# M220.net
KiCad netlist of a schematic drawn in EAGLE
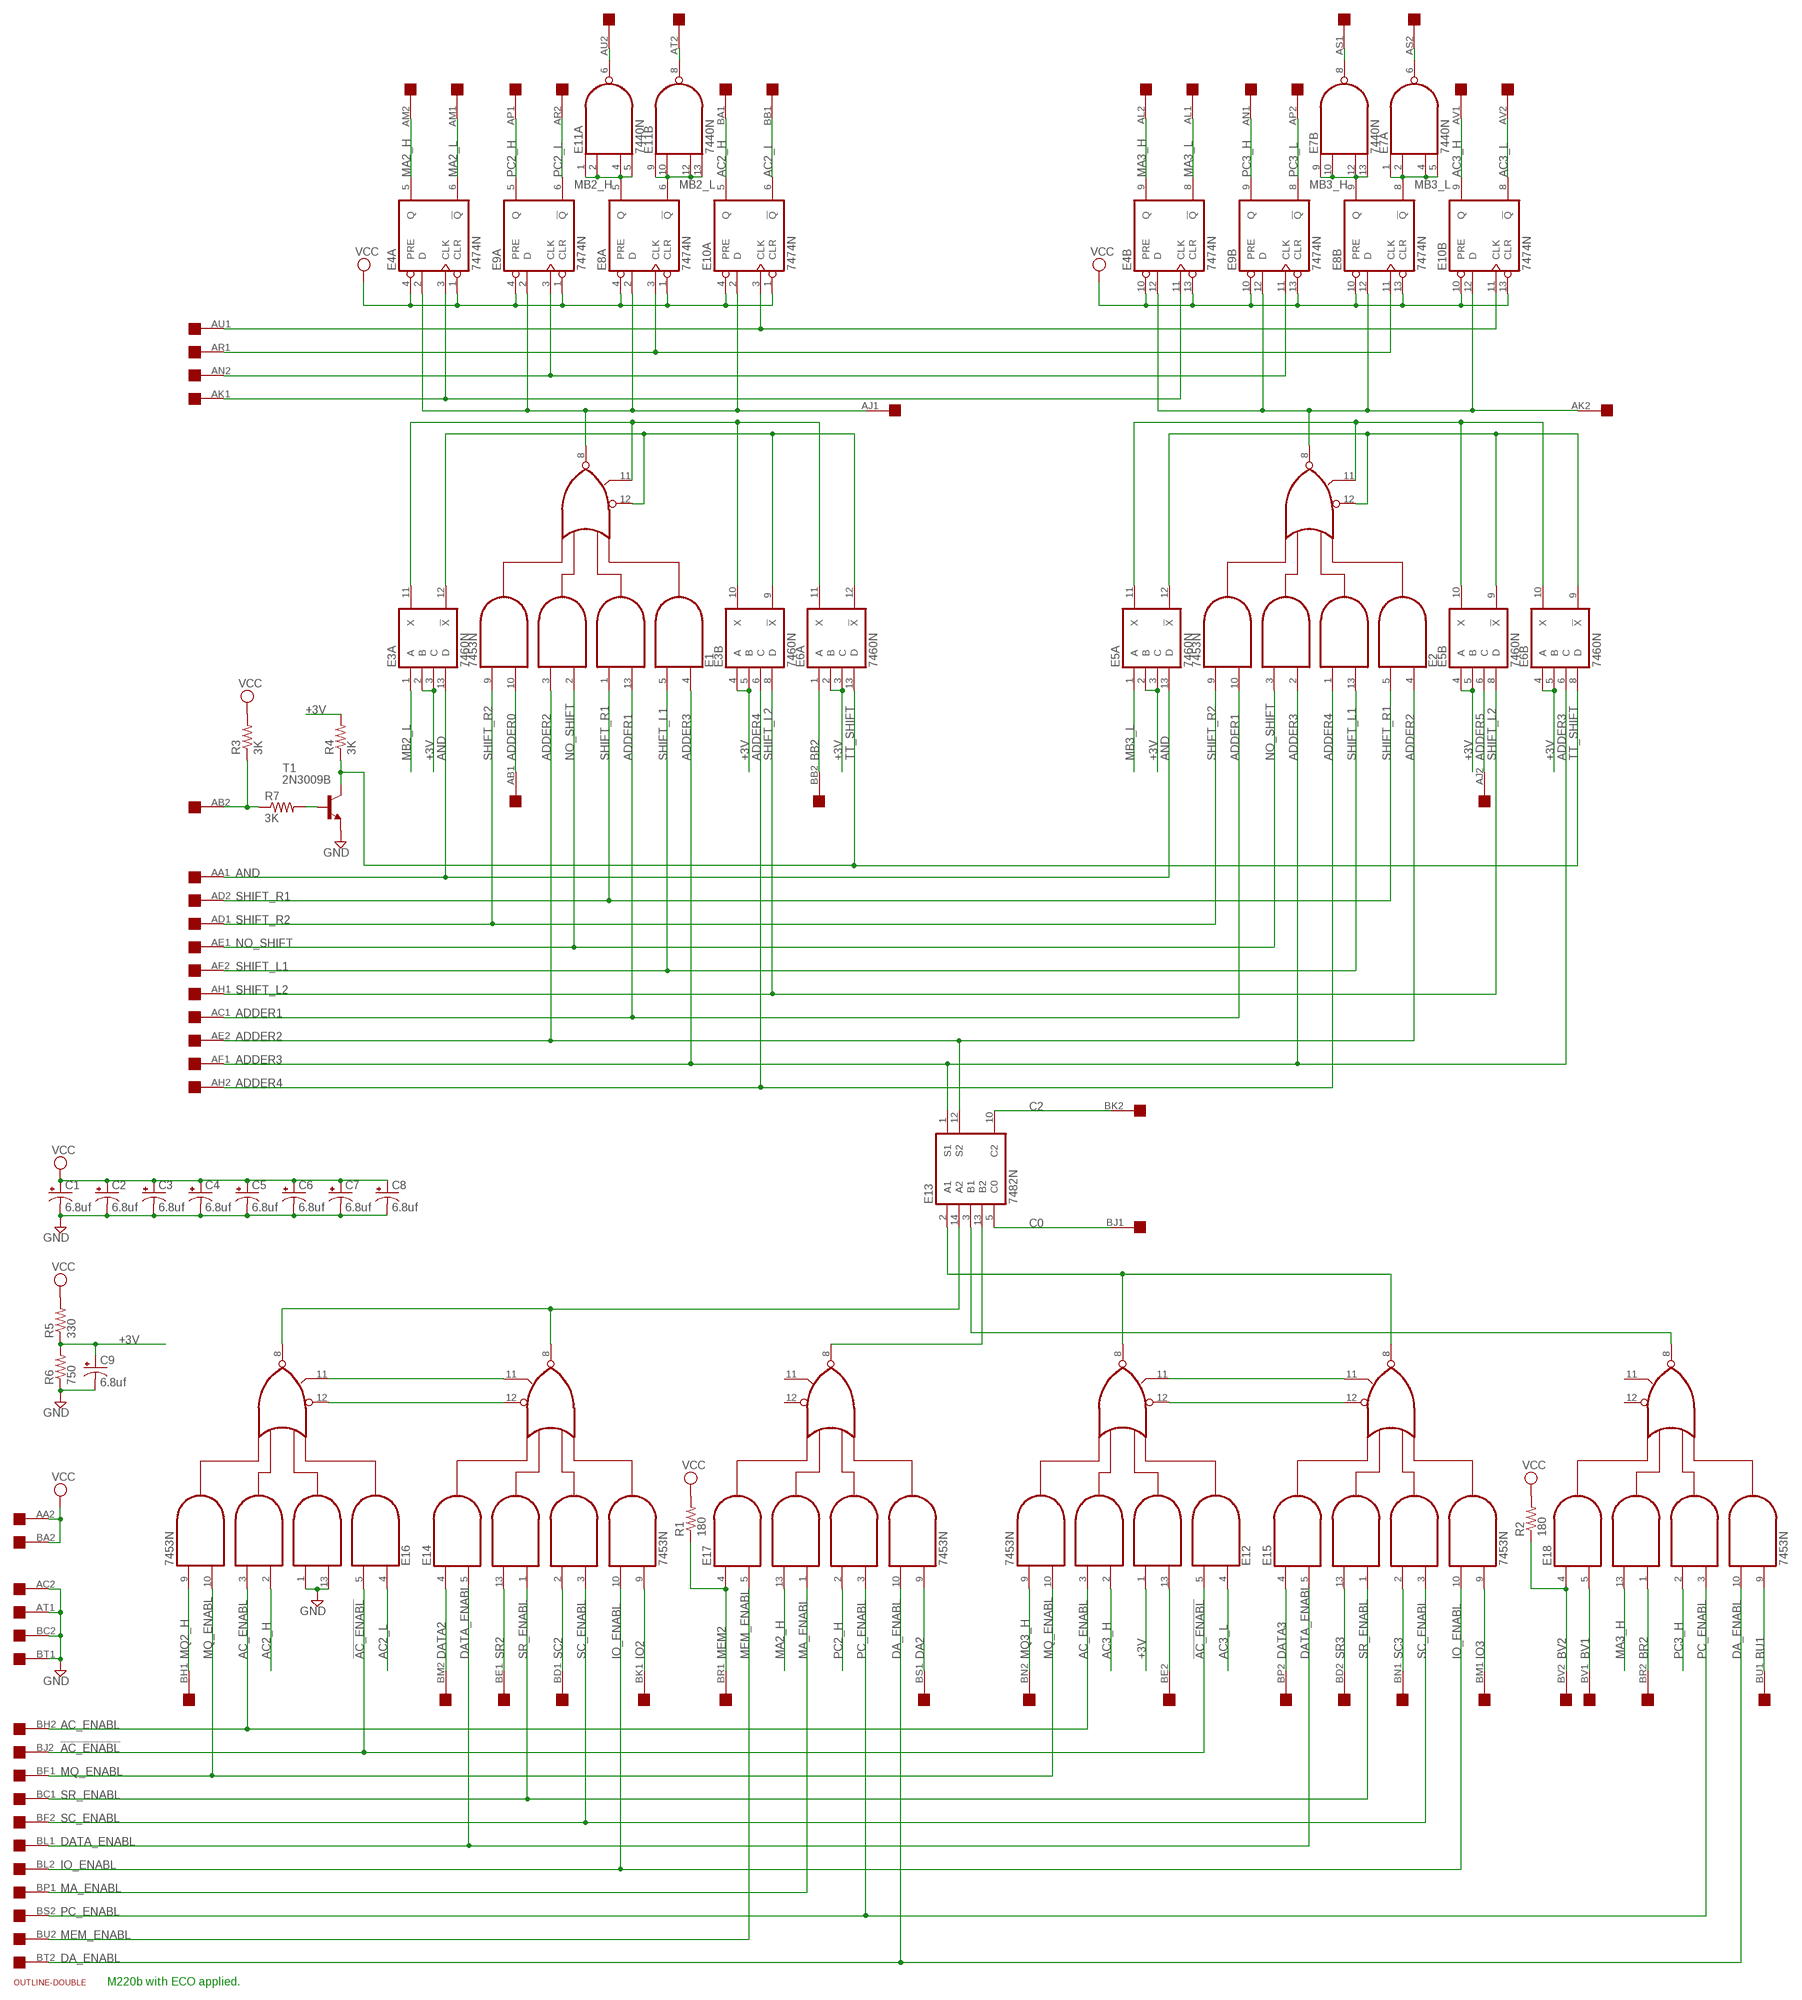
[diagram p0: schematic, sheet 1]

(export (version "E")
  (design (tool "Eeschema 10.0.6"))
  (components
    (comp (ref "C1")
      (value "6.8uf")
      (footprint "eagle-import:E15-5")
      (libsource (lib "eagle-import") (part "CPOL-USE15-5AXIAL"))
    )
    (comp (ref "C2")
      (value "6.8uf")
      (footprint "eagle-import:E15-5")
      (libsource (lib "eagle-import") (part "CPOL-USE15-5AXIAL"))
    )
    (comp (ref "C3")
      (value "6.8uf")
      (footprint "eagle-import:E15-5")
      (libsource (lib "eagle-import") (part "CPOL-USE15-5AXIAL"))
    )
    (comp (ref "C4")
      (value "6.8uf")
      (footprint "eagle-import:E15-5")
      (libsource (lib "eagle-import") (part "CPOL-USE15-5AXIAL"))
    )
    (comp (ref "C5")
      (value "6.8uf")
      (footprint "eagle-import:E15-5")
      (libsource (lib "eagle-import") (part "CPOL-USE15-5AXIAL"))
    )
    (comp (ref "C6")
      (value "6.8uf")
      (footprint "eagle-import:E15-5")
      (libsource (lib "eagle-import") (part "CPOL-USE15-5AXIAL"))
    )
    (comp (ref "C7")
      (value "6.8uf")
      (footprint "eagle-import:E15-5")
      (libsource (lib "eagle-import") (part "CPOL-USE15-5AXIAL"))
    )
    (comp (ref "C8")
      (value "6.8uf")
      (footprint "eagle-import:E15-5")
      (libsource (lib "eagle-import") (part "CPOL-USE15-5AXIAL"))
    )
    (comp (ref "C9")
      (value "6.8uf")
      (footprint "eagle-import:E15-5")
      (libsource (lib "eagle-import") (part "CPOL-USE15-5AXIAL"))
    )
    (comp (ref "E1")
      (value "7453N")
      (footprint "eagle-import:DIL14")
      (libsource (lib "eagle-import") (part "7453N"))
    )
    (comp (ref "E2")
      (value "7453N")
      (footprint "eagle-import:DIL14")
      (libsource (lib "eagle-import") (part "7453N"))
    )
    (comp (ref "E3")
      (value "7460N")
      (footprint "eagle-import:DIL14")
      (libsource (lib "eagle-import") (part "7460N"))
    )
    (comp (ref "E4")
      (value "7474N")
      (footprint "eagle-import:DIL14")
      (libsource (lib "eagle-import") (part "7474NS"))
    )
    (comp (ref "E5")
      (value "7460N")
      (footprint "eagle-import:DIL14")
      (libsource (lib "eagle-import") (part "7460N"))
    )
    (comp (ref "E6")
      (value "7460N")
      (footprint "eagle-import:DIL14")
      (libsource (lib "eagle-import") (part "7460N"))
    )
    (comp (ref "E7")
      (value "7440N")
      (footprint "eagle-import:DIL14")
      (libsource (lib "eagle-import") (part "7420NS"))
    )
    (comp (ref "E8")
      (value "7474N")
      (footprint "eagle-import:DIL14")
      (libsource (lib "eagle-import") (part "7474NS"))
    )
    (comp (ref "E9")
      (value "7474N")
      (footprint "eagle-import:DIL14")
      (libsource (lib "eagle-import") (part "7474NS"))
    )
    (comp (ref "E10")
      (value "7474N")
      (footprint "eagle-import:DIL14")
      (libsource (lib "eagle-import") (part "7474NS"))
    )
    (comp (ref "E11")
      (value "7440N")
      (footprint "eagle-import:DIL14")
      (libsource (lib "eagle-import") (part "7420NS"))
    )
    (comp (ref "E12")
      (value "7453N")
      (footprint "eagle-import:DIL14")
      (libsource (lib "eagle-import") (part "7453N"))
    )
    (comp (ref "E13")
      (value "7482N")
      (footprint "eagle-import:DIL14")
      (libsource (lib "eagle-import") (part "7482N"))
    )
    (comp (ref "E14")
      (value "7453N")
      (footprint "eagle-import:DIL14")
      (libsource (lib "eagle-import") (part "7453N"))
    )
    (comp (ref "E15")
      (value "7453N")
      (footprint "eagle-import:DIL14")
      (libsource (lib "eagle-import") (part "7453N"))
    )
    (comp (ref "E16")
      (value "7453N")
      (footprint "eagle-import:DIL14")
      (libsource (lib "eagle-import") (part "7453N"))
    )
    (comp (ref "E17")
      (value "7453N")
      (footprint "eagle-import:DIL14")
      (libsource (lib "eagle-import") (part "7453N"))
    )
    (comp (ref "E18")
      (value "7453N")
      (footprint "eagle-import:DIL14")
      (libsource (lib "eagle-import") (part "7453N"))
    )
    (comp (ref "R1")
      (value "180")
      (footprint "eagle-import:0207_10")
      (libsource (lib "eagle-import") (part "R-US_0207/10"))
    )
    (comp (ref "R2")
      (value "180")
      (footprint "eagle-import:0207_10")
      (libsource (lib "eagle-import") (part "R-US_0207/10"))
    )
    (comp (ref "R3")
      (value "3K")
      (footprint "eagle-import:0207_10")
      (libsource (lib "eagle-import") (part "R-US_0207/10"))
    )
    (comp (ref "R4")
      (value "3K")
      (footprint "eagle-import:0207_10")
      (libsource (lib "eagle-import") (part "R-US_0207/10"))
    )
    (comp (ref "R5")
      (value "330")
      (footprint "eagle-import:0207_10")
      (libsource (lib "eagle-import") (part "R-US_0207/10"))
    )
    (comp (ref "R6")
      (value "750")
      (footprint "eagle-import:0207_10")
      (libsource (lib "eagle-import") (part "R-US_0207/10"))
    )
    (comp (ref "R7")
      (value "3K")
      (footprint "eagle-import:0207_10")
      (libsource (lib "eagle-import") (part "R-US_0207/10"))
    )
    (comp (ref "T1")
      (value "2N3009B")
      (footprint "eagle-import:TO5")
      (libsource (lib "eagle-import") (part "2N1613"))
    )
    (comp (ref "U$1")
      (value "DOUBLE")
      (footprint "eagle-import:EDGE-CON4")
      (libsource (lib "eagle-import") (part "DOUBLE"))
    )
    (comp (ref "U$2")
      (value "OUTLINE-DOUBLE")
      (footprint "eagle-import:DOUBLE")
      (libsource (lib "eagle-import") (part "OUTLINE-DOUBLE"))
    )
  )
  (nets
    (net (code "1") (name "/+3V") (class "Default")
      (node (ref "C9") (pin "+") (pinfunction "+_+") (pintype "passive"))
      (node (ref "E12") (pin "1") (pinfunction "I4_1") (pintype "input"))
      (node (ref "E3") (pin "2") (pinfunction "B_2") (pintype "input"))
      (node (ref "E3") (pin "3") (pinfunction "C_3") (pintype "input"))
      (node (ref "E3") (pin "4") (pinfunction "A_4") (pintype "input"))
      (node (ref "E3") (pin "5") (pinfunction "B_5") (pintype "input"))
      (node (ref "E5") (pin "2") (pinfunction "B_2") (pintype "input"))
      (node (ref "E5") (pin "3") (pinfunction "C_3") (pintype "input"))
      (node (ref "E5") (pin "4") (pinfunction "A_4") (pintype "input"))
      (node (ref "E5") (pin "5") (pinfunction "B_5") (pintype "input"))
      (node (ref "E6") (pin "2") (pinfunction "B_2") (pintype "input"))
      (node (ref "E6") (pin "3") (pinfunction "C_3") (pintype "input"))
      (node (ref "E6") (pin "4") (pinfunction "A_4") (pintype "input"))
      (node (ref "E6") (pin "5") (pinfunction "B_5") (pintype "input"))
      (node (ref "R4") (pin "2") (pinfunction "2_2") (pintype "passive"))
      (node (ref "R5") (pin "1") (pinfunction "1_1") (pintype "passive"))
      (node (ref "R6") (pin "2") (pinfunction "2_2") (pintype "passive"))
    )
    (net (code "2") (name "/AC2_H") (class "Default")
      (node (ref "E10") (pin "5") (pinfunction "Q_5") (pintype "output"))
      (node (ref "E16") (pin "2") (pinfunction "I5_2") (pintype "input"))
      (node (ref "U$1") (pin "BA1") (pinfunction "1_BA1") (pintype "bidirectional"))
    )
    (net (code "3") (name "/AC2_L") (class "Default")
      (node (ref "E10") (pin "6") (pinfunction "~{Q}_6") (pintype "output"))
      (node (ref "E16") (pin "4") (pinfunction "I1_4") (pintype "input"))
      (node (ref "U$1") (pin "BB1") (pinfunction "1_BB1") (pintype "bidirectional"))
    )
    (net (code "4") (name "/AC3_H") (class "Default")
      (node (ref "E10") (pin "9") (pinfunction "Q_9") (pintype "output"))
      (node (ref "E12") (pin "2") (pinfunction "I5_2") (pintype "input"))
      (node (ref "U$1") (pin "AV1") (pinfunction "1_AV1") (pintype "bidirectional"))
    )
    (net (code "5") (name "/AC3_L") (class "Default")
      (node (ref "E10") (pin "8") (pinfunction "~{Q}_8") (pintype "output"))
      (node (ref "E12") (pin "4") (pinfunction "I1_4") (pintype "input"))
      (node (ref "U$1") (pin "AV2") (pinfunction "1_AV2") (pintype "bidirectional"))
    )
    (net (code "6") (name "/AC_ENABL") (class "Default")
      (node (ref "E12") (pin "3") (pinfunction "I6_3") (pintype "input"))
      (node (ref "E16") (pin "3") (pinfunction "I6_3") (pintype "input"))
      (node (ref "U$1") (pin "BH2") (pinfunction "1_BH2") (pintype "bidirectional"))
    )
    (net (code "7") (name "/ADDER0") (class "Default")
      (node (ref "E1") (pin "10") (pinfunction "I7_10") (pintype "input"))
      (node (ref "U$1") (pin "AB1") (pinfunction "1_AB1") (pintype "bidirectional"))
    )
    (net (code "8") (name "/ADDER1") (class "Default")
      (node (ref "E1") (pin "13") (pinfunction "I3_13") (pintype "input"))
      (node (ref "E2") (pin "10") (pinfunction "I7_10") (pintype "input"))
      (node (ref "U$1") (pin "AC1") (pinfunction "1_AC1") (pintype "bidirectional"))
    )
    (net (code "9") (name "/ADDER2") (class "Default")
      (node (ref "E1") (pin "3") (pinfunction "I6_3") (pintype "input"))
      (node (ref "E13") (pin "12") (pinfunction "S2_12") (pintype "output"))
      (node (ref "E2") (pin "4") (pinfunction "I1_4") (pintype "input"))
      (node (ref "U$1") (pin "AE2") (pinfunction "1_AE2") (pintype "bidirectional"))
    )
    (net (code "10") (name "/ADDER3") (class "Default")
      (node (ref "E1") (pin "4") (pinfunction "I1_4") (pintype "input"))
      (node (ref "E13") (pin "1") (pinfunction "S1_1") (pintype "output"))
      (node (ref "E2") (pin "2") (pinfunction "I5_2") (pintype "input"))
      (node (ref "E6") (pin "6") (pinfunction "C_6") (pintype "input"))
      (node (ref "U$1") (pin "AF1") (pinfunction "1_AF1") (pintype "bidirectional"))
    )
    (net (code "11") (name "/ADDER4") (class "Default")
      (node (ref "E2") (pin "1") (pinfunction "I4_1") (pintype "input"))
      (node (ref "E3") (pin "6") (pinfunction "C_6") (pintype "input"))
      (node (ref "U$1") (pin "AH2") (pinfunction "1_AH2") (pintype "bidirectional"))
    )
    (net (code "12") (name "/ADDER5") (class "Default")
      (node (ref "E5") (pin "6") (pinfunction "C_6") (pintype "input"))
      (node (ref "U$1") (pin "AJ2") (pinfunction "1_AJ2") (pintype "bidirectional"))
    )
    (net (code "13") (name "/AND") (class "Default")
      (node (ref "E3") (pin "13") (pinfunction "D_13") (pintype "input"))
      (node (ref "E5") (pin "13") (pinfunction "D_13") (pintype "input"))
      (node (ref "U$1") (pin "AA1") (pinfunction "1_AA1") (pintype "bidirectional"))
    )
    (net (code "14") (name "/BB2") (class "Default")
      (node (ref "E6") (pin "1") (pinfunction "A_1") (pintype "input"))
      (node (ref "U$1") (pin "BB2") (pinfunction "1_BB2") (pintype "bidirectional"))
    )
    (net (code "15") (name "/BR2") (class "Default")
      (node (ref "E18") (pin "1") (pinfunction "I4_1") (pintype "input"))
      (node (ref "U$1") (pin "BR2") (pinfunction "1_BR2") (pintype "bidirectional"))
    )
    (net (code "16") (name "/BU1") (class "Default")
      (node (ref "E18") (pin "9") (pinfunction "I8_9") (pintype "input"))
      (node (ref "U$1") (pin "BU1") (pinfunction "1_BU1") (pintype "bidirectional"))
    )
    (net (code "17") (name "/BV1") (class "Default")
      (node (ref "E18") (pin "5") (pinfunction "I2_5") (pintype "input"))
      (node (ref "U$1") (pin "BV1") (pinfunction "1_BV1") (pintype "bidirectional"))
    )
    (net (code "18") (name "/BV2") (class "Default")
      (node (ref "E18") (pin "4") (pinfunction "I1_4") (pintype "input"))
      (node (ref "R2") (pin "1") (pinfunction "1_1") (pintype "passive"))
      (node (ref "U$1") (pin "BV2") (pinfunction "1_BV2") (pintype "bidirectional"))
    )
    (net (code "19") (name "/C0") (class "Default")
      (node (ref "E13") (pin "5") (pinfunction "C0_5") (pintype "input"))
      (node (ref "U$1") (pin "BJ1") (pinfunction "1_BJ1") (pintype "bidirectional"))
    )
    (net (code "20") (name "/C2") (class "Default")
      (node (ref "E13") (pin "10") (pinfunction "C2_10") (pintype "output"))
      (node (ref "U$1") (pin "BK2") (pinfunction "1_BK2") (pintype "bidirectional"))
    )
    (net (code "21") (name "/DA2") (class "Default")
      (node (ref "E17") (pin "9") (pinfunction "I8_9") (pintype "input"))
      (node (ref "U$1") (pin "BS1") (pinfunction "1_BS1") (pintype "bidirectional"))
    )
    (net (code "22") (name "/DATA2") (class "Default")
      (node (ref "E14") (pin "4") (pinfunction "I1_4") (pintype "input"))
      (node (ref "U$1") (pin "BM2") (pinfunction "1_BM2") (pintype "bidirectional"))
    )
    (net (code "23") (name "/DATA3") (class "Default")
      (node (ref "E15") (pin "4") (pinfunction "I1_4") (pintype "input"))
      (node (ref "U$1") (pin "BP2") (pinfunction "1_BP2") (pintype "bidirectional"))
    )
    (net (code "24") (name "/DATA_ENABL") (class "Default")
      (node (ref "E14") (pin "5") (pinfunction "I2_5") (pintype "input"))
      (node (ref "E15") (pin "5") (pinfunction "I2_5") (pintype "input"))
      (node (ref "U$1") (pin "BL1") (pinfunction "1_BL1") (pintype "bidirectional"))
    )
    (net (code "25") (name "/DA_ENABL") (class "Default")
      (node (ref "E17") (pin "10") (pinfunction "I7_10") (pintype "input"))
      (node (ref "E18") (pin "10") (pinfunction "I7_10") (pintype "input"))
      (node (ref "U$1") (pin "BT2") (pinfunction "1_BT2") (pintype "bidirectional"))
    )
    (net (code "26") (name "/IO2") (class "Default")
      (node (ref "E14") (pin "9") (pinfunction "I8_9") (pintype "input"))
      (node (ref "U$1") (pin "BK1") (pinfunction "1_BK1") (pintype "bidirectional"))
    )
    (net (code "27") (name "/IO3") (class "Default")
      (node (ref "E15") (pin "9") (pinfunction "I8_9") (pintype "input"))
      (node (ref "U$1") (pin "BM1") (pinfunction "1_BM1") (pintype "bidirectional"))
    )
    (net (code "28") (name "/IO_ENABL") (class "Default")
      (node (ref "E14") (pin "10") (pinfunction "I7_10") (pintype "input"))
      (node (ref "E15") (pin "10") (pinfunction "I7_10") (pintype "input"))
      (node (ref "U$1") (pin "BL2") (pinfunction "1_BL2") (pintype "bidirectional"))
    )
    (net (code "29") (name "/MA2_H") (class "Default")
      (node (ref "E17") (pin "13") (pinfunction "I3_13") (pintype "input"))
      (node (ref "E4") (pin "5") (pinfunction "Q_5") (pintype "output"))
      (node (ref "U$1") (pin "AM2") (pinfunction "1_AM2") (pintype "bidirectional"))
    )
    (net (code "30") (name "/MA2_L") (class "Default")
      (node (ref "E4") (pin "6") (pinfunction "~{Q}_6") (pintype "output"))
      (node (ref "U$1") (pin "AM1") (pinfunction "1_AM1") (pintype "bidirectional"))
    )
    (net (code "31") (name "/MA3_H") (class "Default")
      (node (ref "E18") (pin "13") (pinfunction "I3_13") (pintype "input"))
      (node (ref "E4") (pin "9") (pinfunction "Q_9") (pintype "output"))
      (node (ref "U$1") (pin "AL2") (pinfunction "1_AL2") (pintype "bidirectional"))
    )
    (net (code "32") (name "/MA3_L") (class "Default")
      (node (ref "E4") (pin "8") (pinfunction "~{Q}_8") (pintype "output"))
      (node (ref "U$1") (pin "AL1") (pinfunction "1_AL1") (pintype "bidirectional"))
    )
    (net (code "33") (name "/MA_ENABL") (class "Default")
      (node (ref "E17") (pin "1") (pinfunction "I4_1") (pintype "input"))
      (node (ref "U$1") (pin "BP1") (pinfunction "1_BP1") (pintype "bidirectional"))
    )
    (net (code "34") (name "/MB2_H") (class "Default")
      (node (ref "E11") (pin "1") (pinfunction "I0_1") (pintype "input"))
      (node (ref "E11") (pin "2") (pinfunction "I1_2") (pintype "input"))
      (node (ref "E11") (pin "4") (pinfunction "I2_4") (pintype "input"))
      (node (ref "E11") (pin "5") (pinfunction "I3_5") (pintype "input"))
      (node (ref "E8") (pin "5") (pinfunction "Q_5") (pintype "output"))
    )
    (net (code "35") (name "/MB2_L") (class "Default")
      (node (ref "E11") (pin "10") (pinfunction "I1_10") (pintype "input"))
      (node (ref "E11") (pin "12") (pinfunction "I2_12") (pintype "input"))
      (node (ref "E11") (pin "13") (pinfunction "I3_13") (pintype "input"))
      (node (ref "E11") (pin "9") (pinfunction "I0_9") (pintype "input"))
      (node (ref "E3") (pin "1") (pinfunction "A_1") (pintype "input"))
      (node (ref "E8") (pin "6") (pinfunction "~{Q}_6") (pintype "output"))
    )
    (net (code "36") (name "/MB3_H") (class "Default")
      (node (ref "E7") (pin "10") (pinfunction "I1_10") (pintype "input"))
      (node (ref "E7") (pin "12") (pinfunction "I2_12") (pintype "input"))
      (node (ref "E7") (pin "13") (pinfunction "I3_13") (pintype "input"))
      (node (ref "E7") (pin "9") (pinfunction "I0_9") (pintype "input"))
      (node (ref "E8") (pin "9") (pinfunction "Q_9") (pintype "output"))
    )
    (net (code "37") (name "/MB3_L") (class "Default")
      (node (ref "E5") (pin "1") (pinfunction "A_1") (pintype "input"))
      (node (ref "E7") (pin "1") (pinfunction "I0_1") (pintype "input"))
      (node (ref "E7") (pin "2") (pinfunction "I1_2") (pintype "input"))
      (node (ref "E7") (pin "4") (pinfunction "I2_4") (pintype "input"))
      (node (ref "E7") (pin "5") (pinfunction "I3_5") (pintype "input"))
      (node (ref "E8") (pin "8") (pinfunction "~{Q}_8") (pintype "output"))
    )
    (net (code "38") (name "/MEM2") (class "Default")
      (node (ref "E17") (pin "4") (pinfunction "I1_4") (pintype "input"))
      (node (ref "R1") (pin "1") (pinfunction "1_1") (pintype "passive"))
      (node (ref "U$1") (pin "BR1") (pinfunction "1_BR1") (pintype "bidirectional"))
    )
    (net (code "39") (name "/MEM_ENABL") (class "Default")
      (node (ref "E17") (pin "5") (pinfunction "I2_5") (pintype "input"))
      (node (ref "U$1") (pin "BU2") (pinfunction "1_BU2") (pintype "bidirectional"))
    )
    (net (code "40") (name "/MQ2_H") (class "Default")
      (node (ref "E16") (pin "9") (pinfunction "I8_9") (pintype "input"))
      (node (ref "U$1") (pin "BH1") (pinfunction "1_BH1") (pintype "bidirectional"))
    )
    (net (code "41") (name "/MQ3_H") (class "Default")
      (node (ref "E12") (pin "9") (pinfunction "I8_9") (pintype "input"))
      (node (ref "U$1") (pin "BN2") (pinfunction "1_BN2") (pintype "bidirectional"))
    )
    (net (code "42") (name "/MQ_ENABL") (class "Default")
      (node (ref "E12") (pin "10") (pinfunction "I7_10") (pintype "input"))
      (node (ref "E16") (pin "10") (pinfunction "I7_10") (pintype "input"))
      (node (ref "U$1") (pin "BF1") (pinfunction "1_BF1") (pintype "bidirectional"))
    )
    (net (code "43") (name "/NO_SHIFT") (class "Default")
      (node (ref "E1") (pin "2") (pinfunction "I5_2") (pintype "input"))
      (node (ref "E2") (pin "3") (pinfunction "I6_3") (pintype "input"))
      (node (ref "U$1") (pin "AE1") (pinfunction "1_AE1") (pintype "bidirectional"))
    )
    (net (code "44") (name "/PC2_H") (class "Default")
      (node (ref "E17") (pin "2") (pinfunction "I5_2") (pintype "input"))
      (node (ref "E9") (pin "5") (pinfunction "Q_5") (pintype "output"))
      (node (ref "U$1") (pin "AP1") (pinfunction "1_AP1") (pintype "bidirectional"))
    )
    (net (code "45") (name "/PC2_L") (class "Default")
      (node (ref "E9") (pin "6") (pinfunction "~{Q}_6") (pintype "output"))
      (node (ref "U$1") (pin "AR2") (pinfunction "1_AR2") (pintype "bidirectional"))
    )
    (net (code "46") (name "/PC3_H") (class "Default")
      (node (ref "E18") (pin "2") (pinfunction "I5_2") (pintype "input"))
      (node (ref "E9") (pin "9") (pinfunction "Q_9") (pintype "output"))
      (node (ref "U$1") (pin "AN1") (pinfunction "1_AN1") (pintype "bidirectional"))
    )
    (net (code "47") (name "/PC3_L") (class "Default")
      (node (ref "E9") (pin "8") (pinfunction "~{Q}_8") (pintype "output"))
      (node (ref "U$1") (pin "AP2") (pinfunction "1_AP2") (pintype "bidirectional"))
    )
    (net (code "48") (name "/PC_ENABL") (class "Default")
      (node (ref "E17") (pin "3") (pinfunction "I6_3") (pintype "input"))
      (node (ref "E18") (pin "3") (pinfunction "I6_3") (pintype "input"))
      (node (ref "U$1") (pin "BS2") (pinfunction "1_BS2") (pintype "bidirectional"))
    )
    (net (code "49") (name "/SC2") (class "Default")
      (node (ref "E14") (pin "2") (pinfunction "I5_2") (pintype "input"))
      (node (ref "U$1") (pin "BD1") (pinfunction "1_BD1") (pintype "bidirectional"))
    )
    (net (code "50") (name "/SC3") (class "Default")
      (node (ref "E15") (pin "2") (pinfunction "I5_2") (pintype "input"))
      (node (ref "U$1") (pin "BN1") (pinfunction "1_BN1") (pintype "bidirectional"))
    )
    (net (code "51") (name "/SC_ENABL") (class "Default")
      (node (ref "E14") (pin "3") (pinfunction "I6_3") (pintype "input"))
      (node (ref "E15") (pin "3") (pinfunction "I6_3") (pintype "input"))
      (node (ref "U$1") (pin "BF2") (pinfunction "1_BF2") (pintype "bidirectional"))
    )
    (net (code "52") (name "/SHIFT_L1") (class "Default")
      (node (ref "E1") (pin "5") (pinfunction "I2_5") (pintype "input"))
      (node (ref "E2") (pin "13") (pinfunction "I3_13") (pintype "input"))
      (node (ref "U$1") (pin "AF2") (pinfunction "1_AF2") (pintype "bidirectional"))
    )
    (net (code "53") (name "/SHIFT_L2") (class "Default")
      (node (ref "E3") (pin "8") (pinfunction "D_8") (pintype "input"))
      (node (ref "E5") (pin "8") (pinfunction "D_8") (pintype "input"))
      (node (ref "U$1") (pin "AH1") (pinfunction "1_AH1") (pintype "bidirectional"))
    )
    (net (code "54") (name "/SHIFT_R1") (class "Default")
      (node (ref "E1") (pin "1") (pinfunction "I4_1") (pintype "input"))
      (node (ref "E2") (pin "5") (pinfunction "I2_5") (pintype "input"))
      (node (ref "U$1") (pin "AD2") (pinfunction "1_AD2") (pintype "bidirectional"))
    )
    (net (code "55") (name "/SHIFT_R2") (class "Default")
      (node (ref "E1") (pin "9") (pinfunction "I8_9") (pintype "input"))
      (node (ref "E2") (pin "9") (pinfunction "I8_9") (pintype "input"))
      (node (ref "U$1") (pin "AD1") (pinfunction "1_AD1") (pintype "bidirectional"))
    )
    (net (code "56") (name "/SR2") (class "Default")
      (node (ref "E14") (pin "13") (pinfunction "I3_13") (pintype "input"))
      (node (ref "U$1") (pin "BE1") (pinfunction "1_BE1") (pintype "bidirectional"))
    )
    (net (code "57") (name "/SR3") (class "Default")
      (node (ref "E15") (pin "13") (pinfunction "I3_13") (pintype "input"))
      (node (ref "U$1") (pin "BD2") (pinfunction "1_BD2") (pintype "bidirectional"))
    )
    (net (code "58") (name "/SR_ENABL") (class "Default")
      (node (ref "E14") (pin "1") (pinfunction "I4_1") (pintype "input"))
      (node (ref "E15") (pin "1") (pinfunction "I4_1") (pintype "input"))
      (node (ref "U$1") (pin "BC1") (pinfunction "1_BC1") (pintype "bidirectional"))
    )
    (net (code "59") (name "/TT_SHIFT") (class "Default")
      (node (ref "E6") (pin "13") (pinfunction "D_13") (pintype "input"))
      (node (ref "E6") (pin "8") (pinfunction "D_8") (pintype "input"))
      (node (ref "R4") (pin "1") (pinfunction "1_1") (pintype "passive"))
      (node (ref "T1") (pin "3") (pinfunction "C_3") (pintype "passive"))
    )
    (net (code "60") (name "/~{AC_ENABL}") (class "Default")
      (node (ref "E12") (pin "5") (pinfunction "I2_5") (pintype "input"))
      (node (ref "E16") (pin "5") (pinfunction "I2_5") (pintype "input"))
      (node (ref "U$1") (pin "BJ2") (pinfunction "1_BJ2") (pintype "bidirectional"))
    )
    (net (code "61") (name "GND") (class "Default")
      (node (ref "C1") (pin "-") (pinfunction "-_-") (pintype "passive"))
      (node (ref "C2") (pin "-") (pinfunction "-_-") (pintype "passive"))
      (node (ref "C3") (pin "-") (pinfunction "-_-") (pintype "passive"))
      (node (ref "C4") (pin "-") (pinfunction "-_-") (pintype "passive"))
      (node (ref "C5") (pin "-") (pinfunction "-_-") (pintype "passive"))
      (node (ref "C6") (pin "-") (pinfunction "-_-") (pintype "passive"))
      (node (ref "C7") (pin "-") (pinfunction "-_-") (pintype "passive"))
      (node (ref "C8") (pin "-") (pinfunction "-_-") (pintype "passive"))
      (node (ref "C9") (pin "-") (pinfunction "-_-") (pintype "passive"))
      (node (ref "E16") (pin "1") (pinfunction "I4_1") (pintype "input"))
      (node (ref "E16") (pin "13") (pinfunction "I3_13") (pintype "input"))
      (node (ref "R6") (pin "1") (pinfunction "1_1") (pintype "passive"))
      (node (ref "T1") (pin "1") (pinfunction "E_1") (pintype "passive"))
      (node (ref "U$1") (pin "AC2") (pinfunction "1_AC2") (pintype "bidirectional"))
      (node (ref "U$1") (pin "AT1") (pinfunction "1_AT1") (pintype "bidirectional"))
      (node (ref "U$1") (pin "BC2") (pinfunction "1_BC2") (pintype "bidirectional"))
      (node (ref "U$1") (pin "BT1") (pinfunction "1_BT1") (pintype "bidirectional"))
    )
    (net (code "62") (name "Net-(E1A-I9)") (class "Default")
      (node (ref "E1") (pin "12") (pinfunction "I9_12") (pintype "passive"))
      (node (ref "E3") (pin "12") (pinfunction "~{X}_12") (pintype "output"))
      (node (ref "E3") (pin "9") (pinfunction "~{X}_9") (pintype "output"))
      (node (ref "E6") (pin "12") (pinfunction "~{X}_12") (pintype "output"))
    )
    (net (code "63") (name "Net-(E1A-I10)") (class "Default")
      (node (ref "E1") (pin "11") (pinfunction "I10_11") (pintype "passive"))
      (node (ref "E3") (pin "10") (pinfunction "X_10") (pintype "output"))
      (node (ref "E3") (pin "11") (pinfunction "X_11") (pintype "output"))
      (node (ref "E6") (pin "11") (pinfunction "X_11") (pintype "output"))
    )
    (net (code "64") (name "Net-(E2A-I9)") (class "Default")
      (node (ref "E2") (pin "12") (pinfunction "I9_12") (pintype "passive"))
      (node (ref "E5") (pin "12") (pinfunction "~{X}_12") (pintype "output"))
      (node (ref "E5") (pin "9") (pinfunction "~{X}_9") (pintype "output"))
      (node (ref "E6") (pin "9") (pinfunction "~{X}_9") (pintype "output"))
    )
    (net (code "65") (name "Net-(E2A-I10)") (class "Default")
      (node (ref "E2") (pin "11") (pinfunction "I10_11") (pintype "passive"))
      (node (ref "E5") (pin "10") (pinfunction "X_10") (pintype "output"))
      (node (ref "E5") (pin "11") (pinfunction "X_11") (pintype "output"))
      (node (ref "E6") (pin "10") (pinfunction "X_10") (pintype "output"))
    )
    (net (code "66") (name "Net-(E4A-CLK)") (class "Default")
      (node (ref "E4") (pin "11") (pinfunction "CLK_11") (pintype "input"))
      (node (ref "E4") (pin "3") (pinfunction "CLK_3") (pintype "input"))
      (node (ref "U$1") (pin "AK1") (pinfunction "1_AK1") (pintype "bidirectional"))
    )
    (net (code "67") (name "Net-(E7A-O)") (class "Default")
      (node (ref "E7") (pin "6") (pinfunction "O_6") (pintype "output"))
      (node (ref "U$1") (pin "AS2") (pinfunction "1_AS2") (pintype "bidirectional"))
    )
    (net (code "68") (name "Net-(E7B-O)") (class "Default")
      (node (ref "E7") (pin "8") (pinfunction "O_8") (pintype "output"))
      (node (ref "U$1") (pin "AS1") (pinfunction "1_AS1") (pintype "bidirectional"))
    )
    (net (code "69") (name "Net-(E8A-CLK)") (class "Default")
      (node (ref "E8") (pin "11") (pinfunction "CLK_11") (pintype "input"))
      (node (ref "E8") (pin "3") (pinfunction "CLK_3") (pintype "input"))
      (node (ref "U$1") (pin "AR1") (pinfunction "1_AR1") (pintype "bidirectional"))
    )
    (net (code "70") (name "Net-(E9A-CLK)") (class "Default")
      (node (ref "E9") (pin "11") (pinfunction "CLK_11") (pintype "input"))
      (node (ref "E9") (pin "3") (pinfunction "CLK_3") (pintype "input"))
      (node (ref "U$1") (pin "AN2") (pinfunction "1_AN2") (pintype "bidirectional"))
    )
    (net (code "71") (name "Net-(E10A-CLK)") (class "Default")
      (node (ref "E10") (pin "11") (pinfunction "CLK_11") (pintype "input"))
      (node (ref "E10") (pin "3") (pinfunction "CLK_3") (pintype "input"))
      (node (ref "U$1") (pin "AU1") (pinfunction "1_AU1") (pintype "bidirectional"))
    )
    (net (code "72") (name "Net-(E10A-D)") (class "Default")
      (node (ref "E1") (pin "8") (pinfunction "O_8") (pintype "output"))
      (node (ref "E10") (pin "2") (pinfunction "D_2") (pintype "input"))
      (node (ref "E4") (pin "2") (pinfunction "D_2") (pintype "input"))
      (node (ref "E8") (pin "2") (pinfunction "D_2") (pintype "input"))
      (node (ref "E9") (pin "2") (pinfunction "D_2") (pintype "input"))
      (node (ref "U$1") (pin "AJ1") (pinfunction "1_AJ1") (pintype "bidirectional"))
    )
    (net (code "73") (name "Net-(E10B-D)") (class "Default")
      (node (ref "E10") (pin "12") (pinfunction "D_12") (pintype "input"))
      (node (ref "E2") (pin "8") (pinfunction "O_8") (pintype "output"))
      (node (ref "E4") (pin "12") (pinfunction "D_12") (pintype "input"))
      (node (ref "E8") (pin "12") (pinfunction "D_12") (pintype "input"))
      (node (ref "E9") (pin "12") (pinfunction "D_12") (pintype "input"))
      (node (ref "U$1") (pin "AK2") (pinfunction "1_AK2") (pintype "bidirectional"))
    )
    (net (code "74") (name "Net-(E11A-O)") (class "Default")
      (node (ref "E11") (pin "6") (pinfunction "O_6") (pintype "output"))
      (node (ref "U$1") (pin "AU2") (pinfunction "1_AU2") (pintype "bidirectional"))
    )
    (net (code "75") (name "Net-(E11B-O)") (class "Default")
      (node (ref "E11") (pin "8") (pinfunction "O_8") (pintype "output"))
      (node (ref "U$1") (pin "AT2") (pinfunction "1_AT2") (pintype "bidirectional"))
    )
    (net (code "76") (name "Net-(E12A-I3)") (class "Default")
      (node (ref "E12") (pin "13") (pinfunction "I3_13") (pintype "input"))
      (node (ref "U$1") (pin "BE2") (pinfunction "1_BE2") (pintype "bidirectional"))
    )
    (net (code "77") (name "Net-(E12A-I9)") (class "Default")
      (node (ref "E12") (pin "12") (pinfunction "I9_12") (pintype "passive"))
      (node (ref "E15") (pin "12") (pinfunction "I9_12") (pintype "passive"))
    )
    (net (code "78") (name "Net-(E12A-I10)") (class "Default")
      (node (ref "E12") (pin "11") (pinfunction "I10_11") (pintype "passive"))
      (node (ref "E15") (pin "11") (pinfunction "I10_11") (pintype "passive"))
    )
    (net (code "79") (name "Net-(E12A-O)") (class "Default")
      (node (ref "E12") (pin "8") (pinfunction "O_8") (pintype "output"))
      (node (ref "E13") (pin "2") (pinfunction "A1_2") (pintype "input"))
      (node (ref "E15") (pin "8") (pinfunction "O_8") (pintype "output"))
    )
    (net (code "80") (name "Net-(E13E-A2)") (class "Default")
      (node (ref "E13") (pin "14") (pinfunction "A2_14") (pintype "input"))
      (node (ref "E14") (pin "8") (pinfunction "O_8") (pintype "output"))
      (node (ref "E16") (pin "8") (pinfunction "O_8") (pintype "output"))
    )
    (net (code "81") (name "Net-(E13E-B1)") (class "Default")
      (node (ref "E13") (pin "3") (pinfunction "B1_3") (pintype "input"))
      (node (ref "E18") (pin "8") (pinfunction "O_8") (pintype "output"))
    )
    (net (code "82") (name "Net-(E13E-B2)") (class "Default")
      (node (ref "E13") (pin "13") (pinfunction "B2_13") (pintype "input"))
      (node (ref "E17") (pin "8") (pinfunction "O_8") (pintype "output"))
    )
    (net (code "83") (name "Net-(E14A-I9)") (class "Default")
      (node (ref "E14") (pin "12") (pinfunction "I9_12") (pintype "passive"))
      (node (ref "E16") (pin "12") (pinfunction "I9_12") (pintype "passive"))
    )
    (net (code "84") (name "Net-(E14A-I10)") (class "Default")
      (node (ref "E14") (pin "11") (pinfunction "I10_11") (pintype "passive"))
      (node (ref "E16") (pin "11") (pinfunction "I10_11") (pintype "passive"))
    )
    (net (code "85") (name "Net-(T1-B)") (class "Default")
      (node (ref "R7") (pin "2") (pinfunction "2_2") (pintype "passive"))
      (node (ref "T1") (pin "2") (pinfunction "B_2") (pintype "passive"))
    )
    (net (code "86") (name "Net-(U$1D-1)") (class "Default")
      (node (ref "R3") (pin "1") (pinfunction "1_1") (pintype "passive"))
      (node (ref "R7") (pin "1") (pinfunction "1_1") (pintype "passive"))
      (node (ref "U$1") (pin "AB2") (pinfunction "1_AB2") (pintype "bidirectional"))
    )
    (net (code "87") (name "VCC") (class "Default")
      (node (ref "C1") (pin "+") (pinfunction "+_+") (pintype "passive"))
      (node (ref "C2") (pin "+") (pinfunction "+_+") (pintype "passive"))
      (node (ref "C3") (pin "+") (pinfunction "+_+") (pintype "passive"))
      (node (ref "C4") (pin "+") (pinfunction "+_+") (pintype "passive"))
      (node (ref "C5") (pin "+") (pinfunction "+_+") (pintype "passive"))
      (node (ref "C6") (pin "+") (pinfunction "+_+") (pintype "passive"))
      (node (ref "C7") (pin "+") (pinfunction "+_+") (pintype "passive"))
      (node (ref "C8") (pin "+") (pinfunction "+_+") (pintype "passive"))
      (node (ref "E10") (pin "1") (pinfunction "CLR_1") (pintype "input"))
      (node (ref "E10") (pin "10") (pinfunction "PRE_10") (pintype "input"))
      (node (ref "E10") (pin "13") (pinfunction "CLR_13") (pintype "input"))
      (node (ref "E10") (pin "4") (pinfunction "PRE_4") (pintype "input"))
      (node (ref "E4") (pin "1") (pinfunction "CLR_1") (pintype "input"))
      (node (ref "E4") (pin "10") (pinfunction "PRE_10") (pintype "input"))
      (node (ref "E4") (pin "13") (pinfunction "CLR_13") (pintype "input"))
      (node (ref "E4") (pin "4") (pinfunction "PRE_4") (pintype "input"))
      (node (ref "E8") (pin "1") (pinfunction "CLR_1") (pintype "input"))
      (node (ref "E8") (pin "10") (pinfunction "PRE_10") (pintype "input"))
      (node (ref "E8") (pin "13") (pinfunction "CLR_13") (pintype "input"))
      (node (ref "E8") (pin "4") (pinfunction "PRE_4") (pintype "input"))
      (node (ref "E9") (pin "1") (pinfunction "CLR_1") (pintype "input"))
      (node (ref "E9") (pin "10") (pinfunction "PRE_10") (pintype "input"))
      (node (ref "E9") (pin "13") (pinfunction "CLR_13") (pintype "input"))
      (node (ref "E9") (pin "4") (pinfunction "PRE_4") (pintype "input"))
      (node (ref "R1") (pin "2") (pinfunction "2_2") (pintype "passive"))
      (node (ref "R2") (pin "2") (pinfunction "2_2") (pintype "passive"))
      (node (ref "R3") (pin "2") (pinfunction "2_2") (pintype "passive"))
      (node (ref "R5") (pin "2") (pinfunction "2_2") (pintype "passive"))
      (node (ref "U$1") (pin "AA2") (pinfunction "1_AA2") (pintype "bidirectional"))
      (node (ref "U$1") (pin "BA2") (pinfunction "1_BA2") (pintype "bidirectional"))
    )
    (net (code "88") (name "unconnected-(E17A-I9-Pad12)") (class "Default")
      (node (ref "E17") (pin "12") (pinfunction "I9_12") (pintype "passive"))
    )
    (net (code "89") (name "unconnected-(E17A-I10-Pad11)") (class "Default")
      (node (ref "E17") (pin "11") (pinfunction "I10_11") (pintype "passive"))
    )
    (net (code "90") (name "unconnected-(E18A-I9-Pad12)") (class "Default")
      (node (ref "E18") (pin "12") (pinfunction "I9_12") (pintype "passive"))
    )
    (net (code "91") (name "unconnected-(E18A-I10-Pad11)") (class "Default")
      (node (ref "E18") (pin "11") (pinfunction "I10_11") (pintype "passive"))
    )
  )
)
